# SX1262_e428v03a.net
KiCad netlist of a schematic drawn in Altium Designer
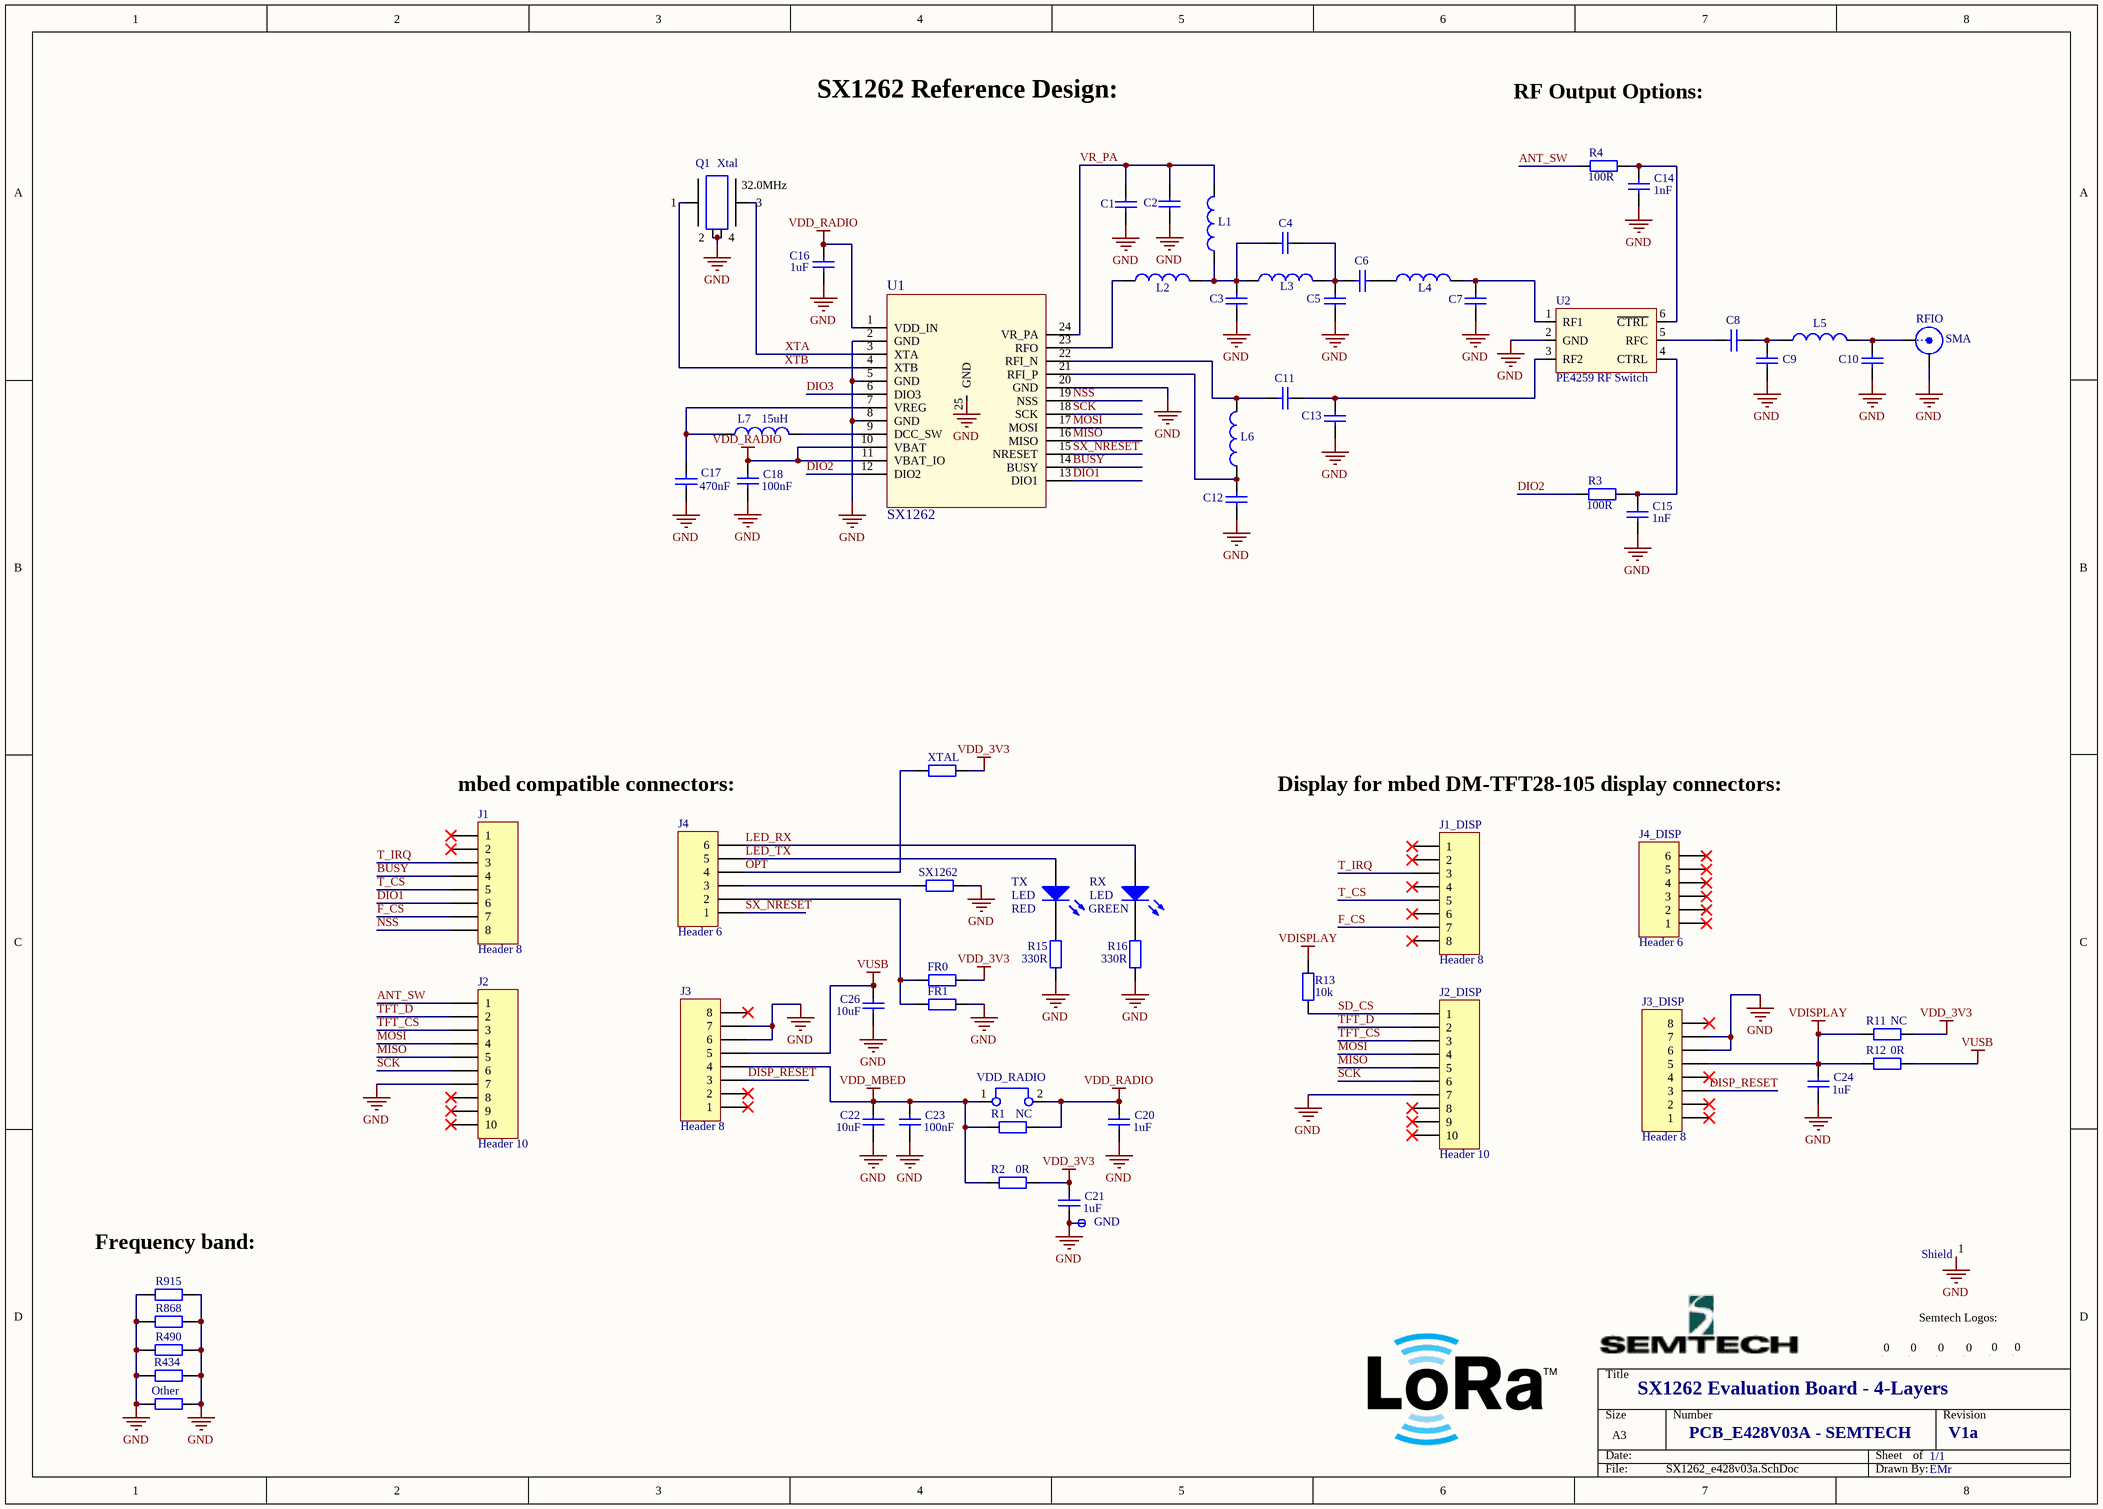
[diagram p0: SX1262_e428v03a.SchDoc]

(export (version "E")
  (design (tool "Eeschema 10.0.6"))
  (components
    (comp (ref "C1")
      (value "Cap")
      (footprint "rlc_402_smd")
      (description "Capacitor SMD")
      (fields (field (name "PUBLISHER") "Altium Limited"))
      (libsource (lib "SX1262_e428v03a") (part "Cap"))
    )
    (comp (ref "C2")
      (value "Cap")
      (footprint "rlc_402_smd")
      (description "Capacitor SMD")
      (fields (field (name "PUBLISHER") "Altium Limited"))
      (libsource (lib "SX1262_e428v03a") (part "Cap"))
    )
    (comp (ref "C3")
      (value "Cap")
      (footprint "rlc_402_smd")
      (description "Capacitor SMD")
      (fields (field (name "PUBLISHER") "Altium Limited"))
      (libsource (lib "SX1262_e428v03a") (part "Cap"))
    )
    (comp (ref "C4")
      (value "Cap")
      (footprint "rlc_402_smd")
      (description "Capacitor SMD")
      (fields (field (name "PUBLISHER") "Altium Limited"))
      (libsource (lib "SX1262_e428v03a") (part "Cap"))
    )
    (comp (ref "C5")
      (value "Cap")
      (footprint "rlc_402_smd")
      (description "Capacitor SMD")
      (fields (field (name "PUBLISHER") "Altium Limited"))
      (libsource (lib "SX1262_e428v03a") (part "Cap"))
    )
    (comp (ref "C6")
      (value "Cap")
      (footprint "rlc_402_smd")
      (description "Capacitor SMD")
      (fields (field (name "PUBLISHER") "Altium Limited"))
      (libsource (lib "SX1262_e428v03a") (part "Cap"))
    )
    (comp (ref "C7")
      (value "Cap")
      (footprint "rlc_402_smd")
      (description "Capacitor SMD")
      (fields (field (name "PUBLISHER") "Altium Limited"))
      (libsource (lib "SX1262_e428v03a") (part "Cap"))
    )
    (comp (ref "C8")
      (value "Cap")
      (footprint "rlc_402_smd")
      (description "Capacitor SMD")
      (fields (field (name "PUBLISHER") "Altium Limited"))
      (libsource (lib "SX1262_e428v03a") (part "Cap"))
    )
    (comp (ref "C9")
      (value "Cap")
      (footprint "rlc_402_smd")
      (description "Capacitor SMD")
      (fields (field (name "PUBLISHER") "Altium Limited"))
      (libsource (lib "SX1262_e428v03a") (part "Cap"))
    )
    (comp (ref "C10")
      (value "Cap")
      (footprint "rlc_402_smd")
      (description "Capacitor SMD")
      (fields (field (name "PUBLISHER") "Altium Limited"))
      (libsource (lib "SX1262_e428v03a") (part "Cap"))
    )
    (comp (ref "C11")
      (value "Cap")
      (footprint "rlc_402_smd")
      (description "Capacitor SMD")
      (fields (field (name "PUBLISHER") "Altium Limited"))
      (libsource (lib "SX1262_e428v03a") (part "Cap"))
    )
    (comp (ref "C12")
      (value "Cap")
      (footprint "rlc_402_smd")
      (description "Capacitor SMD")
      (fields (field (name "PUBLISHER") "Altium Limited"))
      (libsource (lib "SX1262_e428v03a") (part "Cap"))
    )
    (comp (ref "C13")
      (value "Cap")
      (footprint "rlc_402_smd")
      (description "Capacitor SMD")
      (fields (field (name "PUBLISHER") "Altium Limited"))
      (libsource (lib "SX1262_e428v03a") (part "Cap"))
    )
    (comp (ref "C14")
      (value "1nF")
      (footprint "rlc_402_smd")
      (description "Capacitor SMD")
      (fields (field (name "Comment") "Cap") (field (name "PUBLISHER") "Altium Limited"))
      (libsource (lib "SX1262_e428v03a") (part "Cap"))
    )
    (comp (ref "C15")
      (value "1nF")
      (footprint "rlc_402_smd")
      (description "Capacitor SMD")
      (fields (field (name "Comment") "Cap") (field (name "PUBLISHER") "Altium Limited"))
      (libsource (lib "SX1262_e428v03a") (part "Cap"))
    )
    (comp (ref "C16")
      (value "1uF")
      (footprint "rlc_402_smd")
      (description "Capacitor SMD")
      (fields (field (name "Comment") "Cap") (field (name "PUBLISHER") "Altium Limited"))
      (libsource (lib "SX1262_e428v03a") (part "Cap"))
    )
    (comp (ref "C17")
      (value "470nF")
      (footprint "rlc_402_smd")
      (description "Capacitor SMD")
      (fields (field (name "Comment") "Cap") (field (name "PUBLISHER") "Altium Limited"))
      (libsource (lib "SX1262_e428v03a") (part "Cap"))
    )
    (comp (ref "C18")
      (value "100nF")
      (footprint "rlc_402_smd")
      (description "Capacitor SMD")
      (fields (field (name "Comment") "Cap") (field (name "PUBLISHER") "Altium Limited"))
      (libsource (lib "SX1262_e428v03a") (part "Cap"))
    )
    (comp (ref "C20")
      (value "1uF")
      (footprint "rlc_603_smd")
      (description "Capacitor SMD")
      (fields (field (name "Comment") "Cap") (field (name "PUBLISHER") "Altium Limited"))
      (libsource (lib "SX1262_e428v03a") (part "Cap"))
    )
    (comp (ref "C21")
      (value "1uF")
      (footprint "rlc_603_smd")
      (description "Capacitor SMD")
      (fields (field (name "Comment") "Cap") (field (name "PUBLISHER") "Altium Limited"))
      (libsource (lib "SX1262_e428v03a") (part "Cap"))
    )
    (comp (ref "C22")
      (value "10uF")
      (footprint "rlc_805_smd")
      (description "Capacitor SMD")
      (fields (field (name "Comment") "Cap") (field (name "PUBLISHER") "Altium Limited"))
      (libsource (lib "SX1262_e428v03a") (part "Cap"))
    )
    (comp (ref "C23")
      (value "100nF")
      (footprint "rlc_402_smd")
      (description "Capacitor SMD")
      (fields (field (name "Comment") "Cap") (field (name "PUBLISHER") "Altium Limited"))
      (libsource (lib "SX1262_e428v03a") (part "Cap"))
    )
    (comp (ref "C24")
      (value "1uF")
      (footprint "rlc_402_smd")
      (description "Capacitor SMD")
      (fields (field (name "Comment") "Cap") (field (name "PUBLISHER") "Altium Limited"))
      (libsource (lib "SX1262_e428v03a") (part "Cap"))
    )
    (comp (ref "C26")
      (value "10uF")
      (footprint "rlc_805_smd")
      (description "Capacitor SMD")
      (fields (field (name "Comment") "Cap") (field (name "PUBLISHER") "Altium Limited"))
      (libsource (lib "SX1262_e428v03a") (part "Cap"))
    )
    (comp (ref "FR0")
      (value "Resistor")
      (footprint "rlc_402_smd")
      (description "Resistor SMD - IEC symbol version")
      (libsource (lib "SX1262_e428v03a") (part "Resistor"))
    )
    (comp (ref "FR1")
      (value "Resistor")
      (footprint "rlc_402_smd")
      (description "Resistor SMD - IEC symbol version")
      (libsource (lib "SX1262_e428v03a") (part "Resistor"))
    )
    (comp (ref "GND")
      (value "Test Pin")
      (footprint "pin_0.9mm")
      (libsource (lib "SX1262_e428v03a") (part "test_pin"))
    )
    (comp (ref "J1")
      (value "Header 8")
      (footprint "HDR1X8")
      (description "Header, 8-Pin")
      (fields (field (name "PUBLISHER") "Altium Limited"))
      (libsource (lib "SX1262_e428v03a") (part "Header 8"))
    )
    (comp (ref "J1_DISP")
      (value "Header 8")
      (footprint "HDR1X8")
      (description "Header, 8-Pin")
      (fields (field (name "PUBLISHER") "Altium Limited"))
      (libsource (lib "SX1262_e428v03a") (part "Header 8"))
    )
    (comp (ref "J2")
      (value "Header 10")
      (footprint "HDR1X10")
      (description "Header, 10-Pin")
      (fields (field (name "PUBLISHER") "Altium Limited"))
      (libsource (lib "SX1262_e428v03a") (part "Header 10"))
    )
    (comp (ref "J2_DISP")
      (value "Header 10")
      (footprint "HDR1X10")
      (description "Header, 10-Pin")
      (fields (field (name "PUBLISHER") "Altium Limited"))
      (libsource (lib "SX1262_e428v03a") (part "Header 10"))
    )
    (comp (ref "J3")
      (value "Header 8")
      (footprint "HDR1X8")
      (description "Header, 8-Pin")
      (fields (field (name "PUBLISHER") "Altium Limited"))
      (libsource (lib "") (part "Header 8_1"))
    )
    (comp (ref "J3_DISP")
      (value "Header 8")
      (footprint "HDR1X8")
      (description "Header, 8-Pin")
      (fields (field (name "PUBLISHER") "Altium Limited"))
      (libsource (lib "") (part "Header 8_1"))
    )
    (comp (ref "J4")
      (value "Header 6")
      (footprint "HDR1X6")
      (description "Header, 6-Pin")
      (fields (field (name "PUBLISHER") "Altium Limited"))
      (libsource (lib "SX1262_e428v03a") (part "Header 6"))
    )
    (comp (ref "J4_DISP")
      (value "Header 6")
      (footprint "HDR1X6")
      (description "Header, 6-Pin")
      (fields (field (name "PUBLISHER") "Altium Limited"))
      (libsource (lib "SX1262_e428v03a") (part "Header 6"))
    )
    (comp (ref "L1")
      (value "Inductor")
      (footprint "rlc_402_smd")
      (description "Inductor SMD")
      (fields (field (name "PUBLISHER") "Altium Limited"))
      (libsource (lib "SX1262_e428v03a") (part "Inductor"))
    )
    (comp (ref "L2")
      (value "Inductor")
      (footprint "rlc_402_smd")
      (description "Inductor SMD")
      (fields (field (name "PUBLISHER") "Altium Limited"))
      (libsource (lib "SX1262_e428v03a") (part "Inductor"))
    )
    (comp (ref "L3")
      (value "Inductor")
      (footprint "rlc_402_smd")
      (description "Inductor SMD")
      (fields (field (name "PUBLISHER") "Altium Limited"))
      (libsource (lib "SX1262_e428v03a") (part "Inductor"))
    )
    (comp (ref "L4")
      (value "Inductor")
      (footprint "rlc_402_smd")
      (description "Inductor SMD")
      (fields (field (name "PUBLISHER") "Altium Limited"))
      (libsource (lib "SX1262_e428v03a") (part "Inductor"))
    )
    (comp (ref "L5")
      (value "Inductor")
      (footprint "rlc_402_smd")
      (description "Inductor SMD")
      (fields (field (name "PUBLISHER") "Altium Limited"))
      (libsource (lib "SX1262_e428v03a") (part "Inductor"))
    )
    (comp (ref "L6")
      (value "Inductor")
      (footprint "rlc_402_smd")
      (description "Inductor SMD")
      (fields (field (name "PUBLISHER") "Altium Limited"))
      (libsource (lib "SX1262_e428v03a") (part "Inductor"))
    )
    (comp (ref "L7")
      (value "15uH")
      (footprint "rlc_805_smd enlarged")
      (description "Inductor SMD")
      (fields (field (name "Comment") "Inductor") (field (name "PUBLISHER") "Altium Limited"))
      (libsource (lib "SX1262_e428v03a") (part "Inductor"))
    )
    (comp (ref "Logo Bot")
      (value "Logo symbol")
      (footprint "logo_semtech_horiz_size4")
      (description "Schematic symbol for Logo")
      (libsource (lib "SX1262_e428v03a") (part "Logo"))
    )
    (comp (ref "Logo ESD")
      (value "Logo symbol")
      (footprint "Logo ESD")
      (description "Schematic symbol for Logo")
      (libsource (lib "SX1262_e428v03a") (part "Logo"))
    )
    (comp (ref "Logo Recycling1")
      (value "Logo symbol")
      (footprint "Logo Recycling1")
      (description "Schematic symbol for Logo")
      (libsource (lib "SX1262_e428v03a") (part "Logo"))
    )
    (comp (ref "Logo Semtech S")
      (value "Logo symbol")
      (footprint "logo_semtech_horiz_size3")
      (description "Schematic symbol for Logo")
      (libsource (lib "SX1262_e428v03a") (part "Logo"))
    )
    (comp (ref "Logo_LoRA1")
      (value "Logo symbol")
      (footprint "Logo LoRa Size4")
      (description "Schematic symbol for Logo")
      (libsource (lib "SX1262_e428v03a") (part "Logo"))
    )
    (comp (ref "Logo_LoRA2")
      (value "Logo symbol")
      (footprint "Logo LoRa Size3")
      (description "Schematic symbol for Logo")
      (libsource (lib "SX1262_e428v03a") (part "Logo"))
    )
    (comp (ref "Other")
      (value "Resistor")
      (footprint "rlc_402_smd")
      (description "Resistor SMD - IEC symbol version")
      (libsource (lib "") (part "Resistor_1"))
    )
    (comp (ref "Q1")
      (value "Xtal")
      (footprint "nd2016da")
      (description "Crystal with GND pins")
      (fields (field (name "ALTIUM_VALUE") "32.0MHz"))
      (libsource (lib "SX1262_e428v03a") (part "Xtal GND"))
    )
    (comp (ref "R1")
      (value "NC")
      (footprint "rlc_603_smd")
      (description "Resistor SMD - IEC symbol version")
      (fields (field (name "Comment") "Resistor"))
      (libsource (lib "") (part "Resistor_1"))
    )
    (comp (ref "R2")
      (value "0R")
      (footprint "rlc_603_smd")
      (description "Resistor SMD - IEC symbol version")
      (fields (field (name "Comment") "Resistor"))
      (libsource (lib "") (part "Resistor_1"))
    )
    (comp (ref "R3")
      (value "100R")
      (footprint "rlc_402_smd")
      (description "Resistor SMD - IEC symbol version")
      (fields (field (name "Comment") "Resistor"))
      (libsource (lib "") (part "Resistor_1"))
    )
    (comp (ref "R4")
      (value "100R")
      (footprint "rlc_402_smd")
      (description "Resistor SMD - IEC symbol version")
      (fields (field (name "Comment") "Resistor"))
      (libsource (lib "") (part "Resistor_1"))
    )
    (comp (ref "R11")
      (value "NC")
      (footprint "rlc_402_smd")
      (description "Resistor SMD - IEC symbol version")
      (fields (field (name "Comment") "Resistor"))
      (libsource (lib "") (part "Resistor_1"))
    )
    (comp (ref "R12")
      (value "0R")
      (footprint "rlc_402_smd")
      (description "Resistor SMD - IEC symbol version")
      (fields (field (name "Comment") "Resistor"))
      (libsource (lib "") (part "Resistor_1"))
    )
    (comp (ref "R13")
      (value "10k")
      (footprint "rlc_402_smd")
      (description "Resistor SMD - IEC symbol version")
      (fields (field (name "Comment") "Resistor"))
      (libsource (lib "") (part "Resistor_1"))
    )
    (comp (ref "R15")
      (value "330R")
      (footprint "rlc_402_smd")
      (description "Resistor SMD - IEC symbol version")
      (fields (field (name "Comment") "Resistor"))
      (libsource (lib "") (part "Resistor_2"))
    )
    (comp (ref "R16")
      (value "330R")
      (footprint "rlc_402_smd")
      (description "Resistor SMD - IEC symbol version")
      (fields (field (name "Comment") "Resistor"))
      (libsource (lib "") (part "Resistor_2"))
    )
    (comp (ref "R434")
      (value "Resistor")
      (footprint "rlc_402_smd")
      (description "Resistor SMD - IEC symbol version")
      (libsource (lib "") (part "Resistor_1"))
    )
    (comp (ref "R490")
      (value "Resistor")
      (footprint "rlc_402_smd")
      (description "Resistor SMD - IEC symbol version")
      (libsource (lib "") (part "Resistor_1"))
    )
    (comp (ref "R868")
      (value "Resistor")
      (footprint "rlc_402_smd")
      (description "Resistor SMD - IEC symbol version")
      (libsource (lib "") (part "Resistor_1"))
    )
    (comp (ref "R915")
      (value "Resistor")
      (footprint "rlc_402_smd")
      (description "Resistor SMD - IEC symbol version")
      (libsource (lib "") (part "Resistor_1"))
    )
    (comp (ref "RFIO")
      (value "SMA")
      (footprint "SMA_end_launch_1.0mm_9.52mm")
      (description "SMA Straight Connector")
      (fields (field (name "PUBLISHER") "Altium Limited"))
      (libsource (lib "SX1262_e428v03a") (part "SMA"))
    )
    (comp (ref "RX")
      (value "LED")
      (footprint "LGM676 LED")
      (fields (field (name "ALTIUM_VALUE") "GREEN"))
      (libsource (lib "SX1262_e428v03a") (part "LED"))
    )
    (comp (ref "Shield")
      (value "Logo symbol")
      (footprint "BMIS-209-F - Shield - Solder_Mask")
      (description "Shield - EMI Gasket - Standard Surface Mount Shields")
      (libsource (lib "SX1262_e428v03a") (part "Shield"))
    )
    (comp (ref "SX1262")
      (value "Resistor")
      (footprint "rlc_402_smd")
      (description "Resistor SMD - IEC symbol version")
      (libsource (lib "SX1262_e428v03a") (part "Resistor"))
    )
    (comp (ref "TX")
      (value "LED")
      (footprint "LGM676 LED")
      (fields (field (name "ALTIUM_VALUE") "RED"))
      (libsource (lib "SX1262_e428v03a") (part "LED"))
    )
    (comp (ref "U1")
      (value "SX1262")
      (footprint "vqfn24_4x4mm")
      (description "SX1262- Ultra low power RF transceiver")
      (libsource (lib "SX1262_e428v03a") (part "SX126x"))
    )
    (comp (ref "U2")
      (value "PE4259 RF Switch")
      (footprint "SC70-6")
      (description "PE4259 Peregrine RF Switch")
      (libsource (lib "SX1262_e428v03a") (part "PE4259 RF Switch"))
    )
    (comp (ref "VDD_RADIO")
      (value "Jumper")
      (footprint "bridge_254mm")
      (description "Jumper Wire")
      (libsource (lib "SX1262_e428v03a") (part "Jumper"))
    )
    (comp (ref "XTAL")
      (value "Resistor")
      (footprint "rlc_402_smd")
      (description "Resistor SMD - IEC symbol version")
      (libsource (lib "SX1262_e428v03a") (part "Resistor"))
    )
  )
  (nets
    (net (code "1") (name "/ANT_SW") (class "Default")
      (node (ref "J2") (pin "1") (pinfunction "1_1") (pintype "passive"))
      (node (ref "R4") (pin "2") (pinfunction "2_2") (pintype "passive"))
    )
    (net (code "2") (name "/BUSY") (class "Default")
      (node (ref "J1") (pin "4") (pinfunction "4_4") (pintype "passive"))
      (node (ref "U1") (pin "14") (pinfunction "BUSY_14") (pintype "passive"))
    )
    (net (code "3") (name "/DIO1") (class "Default")
      (node (ref "J1") (pin "6") (pinfunction "6_6") (pintype "passive"))
      (node (ref "U1") (pin "13") (pinfunction "DIO1_13") (pintype "passive"))
    )
    (net (code "4") (name "/DIO2") (class "Default")
      (node (ref "R3") (pin "2") (pinfunction "2_2") (pintype "passive"))
      (node (ref "U1") (pin "12") (pinfunction "DIO2_12") (pintype "passive"))
    )
    (net (code "5") (name "/DIO3") (class "Default")
      (node (ref "U1") (pin "6") (pinfunction "DIO3_6") (pintype "passive"))
    )
    (net (code "6") (name "/DISP_RESET") (class "Default")
      (node (ref "J3") (pin "3") (pinfunction "3_3") (pintype "passive"))
      (node (ref "J3_DISP") (pin "3") (pinfunction "3_3") (pintype "passive"))
    )
    (net (code "7") (name "/F_CS") (class "Default")
      (node (ref "J1") (pin "7") (pinfunction "7_7") (pintype "passive"))
      (node (ref "J1_DISP") (pin "7") (pinfunction "7_7") (pintype "passive"))
    )
    (net (code "8") (name "/LED_RX") (class "Default")
      (node (ref "J4") (pin "6") (pinfunction "6_6") (pintype "passive"))
      (node (ref "RX") (pin "1") (pinfunction "A_1") (pintype "passive"))
    )
    (net (code "9") (name "/LED_TX") (class "Default")
      (node (ref "J4") (pin "5") (pinfunction "5_5") (pintype "passive"))
      (node (ref "TX") (pin "1") (pinfunction "A_1") (pintype "passive"))
    )
    (net (code "10") (name "/MISO") (class "Default")
      (node (ref "J2") (pin "5") (pinfunction "5_5") (pintype "passive"))
      (node (ref "J2_DISP") (pin "5") (pinfunction "5_5") (pintype "passive"))
      (node (ref "U1") (pin "16") (pinfunction "MISO_16") (pintype "passive"))
    )
    (net (code "11") (name "/MOSI") (class "Default")
      (node (ref "J2") (pin "4") (pinfunction "4_4") (pintype "passive"))
      (node (ref "J2_DISP") (pin "4") (pinfunction "4_4") (pintype "passive"))
      (node (ref "U1") (pin "17") (pinfunction "MOSI_17") (pintype "passive"))
    )
    (net (code "12") (name "/NSS") (class "Default")
      (node (ref "J1") (pin "8") (pinfunction "8_8") (pintype "passive"))
      (node (ref "U1") (pin "19") (pinfunction "NSS_19") (pintype "passive"))
    )
    (net (code "13") (name "/OPT") (class "Default")
      (node (ref "J4") (pin "4") (pinfunction "4_4") (pintype "passive"))
      (node (ref "XTAL") (pin "2") (pinfunction "2_2") (pintype "passive"))
    )
    (net (code "14") (name "/SCK") (class "Default")
      (node (ref "J2") (pin "6") (pinfunction "6_6") (pintype "passive"))
      (node (ref "J2_DISP") (pin "6") (pinfunction "6_6") (pintype "passive"))
      (node (ref "U1") (pin "18") (pinfunction "SCK_18") (pintype "passive"))
    )
    (net (code "15") (name "/SD_CS") (class "Default")
      (node (ref "J2_DISP") (pin "1") (pinfunction "1_1") (pintype "passive"))
      (node (ref "R13") (pin "2") (pinfunction "2_2") (pintype "passive"))
    )
    (net (code "16") (name "/SX_NRESET") (class "Default")
      (node (ref "J4") (pin "1") (pinfunction "1_1") (pintype "passive"))
      (node (ref "U1") (pin "15") (pinfunction "NRESET_15") (pintype "passive"))
    )
    (net (code "17") (name "/TFT_CS") (class "Default")
      (node (ref "J2") (pin "3") (pinfunction "3_3") (pintype "passive"))
      (node (ref "J2_DISP") (pin "3") (pinfunction "3_3") (pintype "passive"))
    )
    (net (code "18") (name "/TFT_D") (class "Default")
      (node (ref "J2") (pin "2") (pinfunction "2_2") (pintype "passive"))
      (node (ref "J2_DISP") (pin "2") (pinfunction "2_2") (pintype "passive"))
    )
    (net (code "19") (name "/T_CS") (class "Default")
      (node (ref "J1") (pin "5") (pinfunction "5_5") (pintype "passive"))
      (node (ref "J1_DISP") (pin "5") (pinfunction "5_5") (pintype "passive"))
    )
    (net (code "20") (name "/T_IRQ") (class "Default")
      (node (ref "J1") (pin "3") (pinfunction "3_3") (pintype "passive"))
      (node (ref "J1_DISP") (pin "3") (pinfunction "3_3") (pintype "passive"))
    )
    (net (code "21") (name "/VR_PA") (class "Default")
      (node (ref "C1") (pin "2") (pinfunction "2_2") (pintype "passive"))
      (node (ref "C2") (pin "2") (pinfunction "2_2") (pintype "passive"))
      (node (ref "L1") (pin "2") (pinfunction "2_2") (pintype "passive"))
      (node (ref "U1") (pin "24") (pinfunction "VR_PA_24") (pintype "power_in"))
    )
    (net (code "22") (name "/XTA") (class "Default")
      (node (ref "Q1") (pin "3") (pinfunction "3_3") (pintype "passive"))
      (node (ref "U1") (pin "3") (pinfunction "XTA_3") (pintype "passive"))
    )
    (net (code "24") (name "/XTB") (class "Default")
      (node (ref "Q1") (pin "1") (pinfunction "1_1") (pintype "passive"))
      (node (ref "U1") (pin "4") (pinfunction "XTB_4") (pintype "passive"))
    )
    (net (code "25") (name "GND") (class "Default")
      (node (ref "C1") (pin "1") (pinfunction "1_1") (pintype "passive"))
      (node (ref "C10") (pin "1") (pinfunction "1_1") (pintype "passive"))
      (node (ref "C12") (pin "1") (pinfunction "1_1") (pintype "passive"))
      (node (ref "C13") (pin "1") (pinfunction "1_1") (pintype "passive"))
      (node (ref "C14") (pin "2") (pinfunction "2_2") (pintype "passive"))
      (node (ref "C15") (pin "2") (pinfunction "2_2") (pintype "passive"))
      (node (ref "C16") (pin "1") (pinfunction "1_1") (pintype "passive"))
      (node (ref "C17") (pin "1") (pinfunction "1_1") (pintype "passive"))
      (node (ref "C18") (pin "1") (pinfunction "1_1") (pintype "passive"))
      (node (ref "C2") (pin "1") (pinfunction "1_1") (pintype "passive"))
      (node (ref "C20") (pin "1") (pinfunction "1_1") (pintype "passive"))
      (node (ref "C21") (pin "1") (pinfunction "1_1") (pintype "passive"))
      (node (ref "C22") (pin "1") (pinfunction "1_1") (pintype "passive"))
      (node (ref "C23") (pin "1") (pinfunction "1_1") (pintype "passive"))
      (node (ref "C24") (pin "1") (pinfunction "1_1") (pintype "passive"))
      (node (ref "C26") (pin "1") (pinfunction "1_1") (pintype "passive"))
      (node (ref "C3") (pin "1") (pinfunction "1_1") (pintype "passive"))
      (node (ref "C5") (pin "1") (pinfunction "1_1") (pintype "passive"))
      (node (ref "C7") (pin "1") (pinfunction "1_1") (pintype "passive"))
      (node (ref "C9") (pin "1") (pinfunction "1_1") (pintype "passive"))
      (node (ref "FR1") (pin "1") (pinfunction "1_1") (pintype "passive"))
      (node (ref "GND") (pin "1") (pinfunction "pin_1") (pintype "passive"))
      (node (ref "J2") (pin "7") (pinfunction "7_7") (pintype "passive"))
      (node (ref "J2_DISP") (pin "7") (pinfunction "7_7") (pintype "passive"))
      (node (ref "J3") (pin "6") (pinfunction "6_6") (pintype "passive"))
      (node (ref "J3") (pin "7") (pinfunction "7_7") (pintype "passive"))
      (node (ref "J3_DISP") (pin "6") (pinfunction "6_6") (pintype "passive"))
      (node (ref "J3_DISP") (pin "7") (pinfunction "7_7") (pintype "passive"))
      (node (ref "Other") (pin "1") (pinfunction "1_1") (pintype "passive"))
      (node (ref "Other") (pin "2") (pinfunction "2_2") (pintype "passive"))
      (node (ref "Q1") (pin "2") (pinfunction "2_2") (pintype "passive"))
      (node (ref "Q1") (pin "4") (pinfunction "4_4") (pintype "passive"))
      (node (ref "R15") (pin "1") (pinfunction "1_1") (pintype "passive"))
      (node (ref "R16") (pin "1") (pinfunction "1_1") (pintype "passive"))
      (node (ref "R434") (pin "1") (pinfunction "1_1") (pintype "passive"))
      (node (ref "R434") (pin "2") (pinfunction "2_2") (pintype "passive"))
      (node (ref "R490") (pin "1") (pinfunction "1_1") (pintype "passive"))
      (node (ref "R490") (pin "2") (pinfunction "2_2") (pintype "passive"))
      (node (ref "R868") (pin "1") (pinfunction "1_1") (pintype "passive"))
      (node (ref "R868") (pin "2") (pinfunction "2_2") (pintype "passive"))
      (node (ref "R915") (pin "1") (pinfunction "1_1") (pintype "passive"))
      (node (ref "R915") (pin "2") (pinfunction "2_2") (pintype "passive"))
      (node (ref "RFIO") (pin "2") (pinfunction "GND_2") (pintype "passive"))
      (node (ref "SX1262") (pin "1") (pinfunction "1_1") (pintype "passive"))
      (node (ref "Shield") (pin "1") (pinfunction "1_1") (pintype "passive"))
      (node (ref "U1") (pin "2") (pinfunction "GND_2") (pintype "passive"))
      (node (ref "U1") (pin "20") (pinfunction "GND_20") (pintype "passive"))
      (node (ref "U1") (pin "25") (pinfunction "GND_25") (pintype "passive"))
      (node (ref "U1") (pin "5") (pinfunction "GND_5") (pintype "passive"))
      (node (ref "U1") (pin "8") (pinfunction "GND_8") (pintype "passive"))
      (node (ref "U2") (pin "2") (pinfunction "GND_2") (pintype "passive"))
    )
    (net (code "26") (name "Net-(C3-Pad2)") (class "Default")
      (node (ref "C3") (pin "2") (pinfunction "2_2") (pintype "passive"))
      (node (ref "C4") (pin "2") (pinfunction "2_2") (pintype "passive"))
      (node (ref "L1") (pin "1") (pinfunction "1_1") (pintype "passive"))
      (node (ref "L2") (pin "2") (pinfunction "2_2") (pintype "passive"))
      (node (ref "L3") (pin "1") (pinfunction "1_1") (pintype "passive"))
    )
    (net (code "27") (name "Net-(C4-Pad1)") (class "Default")
      (node (ref "C4") (pin "1") (pinfunction "1_1") (pintype "passive"))
      (node (ref "C5") (pin "2") (pinfunction "2_2") (pintype "passive"))
      (node (ref "C6") (pin "2") (pinfunction "2_2") (pintype "passive"))
      (node (ref "L3") (pin "2") (pinfunction "2_2") (pintype "passive"))
    )
    (net (code "28") (name "Net-(C6-Pad1)") (class "Default")
      (node (ref "C6") (pin "1") (pinfunction "1_1") (pintype "passive"))
      (node (ref "L4") (pin "1") (pinfunction "1_1") (pintype "passive"))
    )
    (net (code "29") (name "Net-(C8-Pad1)") (class "Default")
      (node (ref "C8") (pin "1") (pinfunction "1_1") (pintype "passive"))
      (node (ref "C9") (pin "2") (pinfunction "2_2") (pintype "passive"))
      (node (ref "L5") (pin "1") (pinfunction "1_1") (pintype "passive"))
    )
    (net (code "30") (name "Net-(FR0-Pad2)") (class "Default")
      (node (ref "FR0") (pin "2") (pinfunction "2_2") (pintype "passive"))
      (node (ref "FR1") (pin "2") (pinfunction "2_2") (pintype "passive"))
      (node (ref "J4") (pin "2") (pinfunction "2_2") (pintype "passive"))
    )
    (net (code "31") (name "Net-(J4-Pad3)") (class "Default")
      (node (ref "J4") (pin "3") (pinfunction "3_3") (pintype "passive"))
      (node (ref "SX1262") (pin "2") (pinfunction "2_2") (pintype "passive"))
    )
    (net (code "32") (name "Net-(RFIO-Signal)") (class "Default")
      (node (ref "C10") (pin "2") (pinfunction "2_2") (pintype "passive"))
      (node (ref "L5") (pin "2") (pinfunction "2_2") (pintype "passive"))
      (node (ref "RFIO") (pin "1") (pinfunction "Signal_1") (pintype "passive"))
    )
    (net (code "33") (name "Net-(RX-K)") (class "Default")
      (node (ref "R16") (pin "2") (pinfunction "2_2") (pintype "passive"))
      (node (ref "RX") (pin "2") (pinfunction "K_2") (pintype "passive"))
    )
    (net (code "34") (name "Net-(TX-K)") (class "Default")
      (node (ref "R15") (pin "2") (pinfunction "2_2") (pintype "passive"))
      (node (ref "TX") (pin "2") (pinfunction "K_2") (pintype "passive"))
    )
    (net (code "35") (name "Net-(U1-DCC_SW)") (class "Default")
      (node (ref "L7") (pin "2") (pinfunction "2_2") (pintype "passive"))
      (node (ref "U1") (pin "9") (pinfunction "DCC_SW_9") (pintype "power_in"))
    )
    (net (code "36") (name "Net-(U1-RFI_N)") (class "Default")
      (node (ref "C11") (pin "2") (pinfunction "2_2") (pintype "passive"))
      (node (ref "L6") (pin "2") (pinfunction "2_2") (pintype "passive"))
      (node (ref "U1") (pin "22") (pinfunction "RFI_N_22") (pintype "passive"))
    )
    (net (code "37") (name "Net-(U1-RFI_P)") (class "Default")
      (node (ref "C12") (pin "2") (pinfunction "2_2") (pintype "passive"))
      (node (ref "L6") (pin "1") (pinfunction "1_1") (pintype "passive"))
      (node (ref "U1") (pin "21") (pinfunction "RFI_P_21") (pintype "passive"))
    )
    (net (code "38") (name "Net-(U1-RFO)") (class "Default")
      (node (ref "L2") (pin "1") (pinfunction "1_1") (pintype "passive"))
      (node (ref "U1") (pin "23") (pinfunction "RFO_23") (pintype "passive"))
    )
    (net (code "39") (name "Net-(U1-VREG)") (class "Default")
      (node (ref "C17") (pin "2") (pinfunction "2_2") (pintype "passive"))
      (node (ref "L7") (pin "1") (pinfunction "1_1") (pintype "passive"))
      (node (ref "U1") (pin "7") (pinfunction "VREG_7") (pintype "power_in"))
    )
    (net (code "40") (name "Net-(U2-CTRL)") (class "Default")
      (node (ref "C15") (pin "1") (pinfunction "1_1") (pintype "passive"))
      (node (ref "R3") (pin "1") (pinfunction "1_1") (pintype "passive"))
      (node (ref "U2") (pin "4") (pinfunction "CTRL_4") (pintype "passive"))
    )
    (net (code "41") (name "Net-(U2-RF1)") (class "Default")
      (node (ref "C7") (pin "2") (pinfunction "2_2") (pintype "passive"))
      (node (ref "L4") (pin "2") (pinfunction "2_2") (pintype "passive"))
      (node (ref "U2") (pin "1") (pinfunction "RF1_1") (pintype "passive"))
    )
    (net (code "42") (name "Net-(U2-RF2)") (class "Default")
      (node (ref "C11") (pin "1") (pinfunction "1_1") (pintype "passive"))
      (node (ref "C13") (pin "2") (pinfunction "2_2") (pintype "passive"))
      (node (ref "U2") (pin "3") (pinfunction "RF2_3") (pintype "passive"))
    )
    (net (code "43") (name "Net-(U2-RFC)") (class "Default")
      (node (ref "C8") (pin "2") (pinfunction "2_2") (pintype "passive"))
      (node (ref "U2") (pin "5") (pinfunction "RFC_5") (pintype "passive"))
    )
    (net (code "44") (name "Net-(U2-~{CTRL})") (class "Default")
      (node (ref "C14") (pin "1") (pinfunction "1_1") (pintype "passive"))
      (node (ref "R4") (pin "1") (pinfunction "1_1") (pintype "passive"))
      (node (ref "U2") (pin "6") (pinfunction "~{CTRL}_6") (pintype "passive"))
    )
    (net (code "45") (name "VDD_3V3") (class "Default")
      (node (ref "C21") (pin "2") (pinfunction "2_2") (pintype "passive"))
      (node (ref "FR0") (pin "1") (pinfunction "1_1") (pintype "passive"))
      (node (ref "R11") (pin "1") (pinfunction "1_1") (pintype "passive"))
      (node (ref "R2") (pin "1") (pinfunction "1_1") (pintype "passive"))
      (node (ref "XTAL") (pin "1") (pinfunction "1_1") (pintype "passive"))
    )
    (net (code "46") (name "VDD_MBED") (class "Default")
      (node (ref "C22") (pin "2") (pinfunction "2_2") (pintype "passive"))
      (node (ref "C23") (pin "2") (pinfunction "2_2") (pintype "passive"))
      (node (ref "J3") (pin "4") (pinfunction "4_4") (pintype "passive"))
      (node (ref "R1") (pin "2") (pinfunction "2_2") (pintype "passive"))
      (node (ref "R2") (pin "2") (pinfunction "2_2") (pintype "passive"))
      (node (ref "VDD_RADIO") (pin "1") (pinfunction "1_1") (pintype "passive"))
    )
    (net (code "47") (name "VDD_RADIO") (class "Default")
      (node (ref "C16") (pin "2") (pinfunction "2_2") (pintype "passive"))
      (node (ref "C18") (pin "2") (pinfunction "2_2") (pintype "passive"))
      (node (ref "C20") (pin "2") (pinfunction "2_2") (pintype "passive"))
      (node (ref "R1") (pin "1") (pinfunction "1_1") (pintype "passive"))
      (node (ref "U1") (pin "1") (pinfunction "VDD_IN_1") (pintype "power_in"))
      (node (ref "U1") (pin "10") (pinfunction "VBAT_10") (pintype "power_in"))
      (node (ref "U1") (pin "11") (pinfunction "VBAT_IO_11") (pintype "power_in"))
      (node (ref "VDD_RADIO") (pin "2") (pinfunction "2_2") (pintype "passive"))
    )
    (net (code "48") (name "VDISPLAY") (class "Default")
      (node (ref "C24") (pin "2") (pinfunction "2_2") (pintype "passive"))
      (node (ref "J3_DISP") (pin "5") (pinfunction "5_5") (pintype "passive"))
      (node (ref "R11") (pin "2") (pinfunction "2_2") (pintype "passive"))
      (node (ref "R12") (pin "2") (pinfunction "2_2") (pintype "passive"))
      (node (ref "R13") (pin "1") (pinfunction "1_1") (pintype "passive"))
    )
    (net (code "49") (name "VUSB") (class "Default")
      (node (ref "C26") (pin "2") (pinfunction "2_2") (pintype "passive"))
      (node (ref "J3") (pin "5") (pinfunction "5_5") (pintype "passive"))
      (node (ref "R12") (pin "1") (pinfunction "1_1") (pintype "passive"))
    )
    (net (code "50") (name "unconnected-(J1-Pad1)") (class "Default")
      (node (ref "J1") (pin "1") (pinfunction "1_1") (pintype "passive+no_connect"))
    )
    (net (code "51") (name "unconnected-(J1-Pad2)") (class "Default")
      (node (ref "J1") (pin "2") (pinfunction "2_2") (pintype "passive+no_connect"))
    )
    (net (code "52") (name "unconnected-(J1_DISP-Pad1)") (class "Default")
      (node (ref "J1_DISP") (pin "1") (pinfunction "1_1") (pintype "passive+no_connect"))
    )
    (net (code "53") (name "unconnected-(J1_DISP-Pad2)") (class "Default")
      (node (ref "J1_DISP") (pin "2") (pinfunction "2_2") (pintype "passive+no_connect"))
    )
    (net (code "54") (name "unconnected-(J1_DISP-Pad4)") (class "Default")
      (node (ref "J1_DISP") (pin "4") (pinfunction "4_4") (pintype "passive+no_connect"))
    )
    (net (code "55") (name "unconnected-(J1_DISP-Pad6)") (class "Default")
      (node (ref "J1_DISP") (pin "6") (pinfunction "6_6") (pintype "passive+no_connect"))
    )
    (net (code "56") (name "unconnected-(J1_DISP-Pad8)") (class "Default")
      (node (ref "J1_DISP") (pin "8") (pinfunction "8_8") (pintype "passive+no_connect"))
    )
    (net (code "57") (name "unconnected-(J2-Pad8)") (class "Default")
      (node (ref "J2") (pin "8") (pinfunction "8_8") (pintype "passive+no_connect"))
    )
    (net (code "58") (name "unconnected-(J2-Pad9)") (class "Default")
      (node (ref "J2") (pin "9") (pinfunction "9_9") (pintype "passive+no_connect"))
    )
    (net (code "59") (name "unconnected-(J2-Pad10)") (class "Default")
      (node (ref "J2") (pin "10") (pinfunction "10_10") (pintype "passive+no_connect"))
    )
    (net (code "60") (name "unconnected-(J2_DISP-Pad8)") (class "Default")
      (node (ref "J2_DISP") (pin "8") (pinfunction "8_8") (pintype "passive+no_connect"))
    )
    (net (code "61") (name "unconnected-(J2_DISP-Pad9)") (class "Default")
      (node (ref "J2_DISP") (pin "9") (pinfunction "9_9") (pintype "passive+no_connect"))
    )
    (net (code "62") (name "unconnected-(J2_DISP-Pad10)") (class "Default")
      (node (ref "J2_DISP") (pin "10") (pinfunction "10_10") (pintype "passive+no_connect"))
    )
    (net (code "63") (name "unconnected-(J3-Pad1)") (class "Default")
      (node (ref "J3") (pin "1") (pinfunction "1_1") (pintype "passive+no_connect"))
    )
    (net (code "64") (name "unconnected-(J3-Pad2)") (class "Default")
      (node (ref "J3") (pin "2") (pinfunction "2_2") (pintype "passive+no_connect"))
    )
    (net (code "65") (name "unconnected-(J3-Pad8)") (class "Default")
      (node (ref "J3") (pin "8") (pinfunction "8_8") (pintype "passive+no_connect"))
    )
    (net (code "66") (name "unconnected-(J3_DISP-Pad1)") (class "Default")
      (node (ref "J3_DISP") (pin "1") (pinfunction "1_1") (pintype "passive+no_connect"))
    )
    (net (code "67") (name "unconnected-(J3_DISP-Pad2)") (class "Default")
      (node (ref "J3_DISP") (pin "2") (pinfunction "2_2") (pintype "passive+no_connect"))
    )
    (net (code "68") (name "unconnected-(J3_DISP-Pad4)") (class "Default")
      (node (ref "J3_DISP") (pin "4") (pinfunction "4_4") (pintype "passive+no_connect"))
    )
    (net (code "69") (name "unconnected-(J3_DISP-Pad8)") (class "Default")
      (node (ref "J3_DISP") (pin "8") (pinfunction "8_8") (pintype "passive+no_connect"))
    )
    (net (code "70") (name "unconnected-(J4_DISP-Pad1)") (class "Default")
      (node (ref "J4_DISP") (pin "1") (pinfunction "1_1") (pintype "passive+no_connect"))
    )
    (net (code "71") (name "unconnected-(J4_DISP-Pad2)") (class "Default")
      (node (ref "J4_DISP") (pin "2") (pinfunction "2_2") (pintype "passive+no_connect"))
    )
    (net (code "72") (name "unconnected-(J4_DISP-Pad3)") (class "Default")
      (node (ref "J4_DISP") (pin "3") (pinfunction "3_3") (pintype "passive+no_connect"))
    )
    (net (code "73") (name "unconnected-(J4_DISP-Pad4)") (class "Default")
      (node (ref "J4_DISP") (pin "4") (pinfunction "4_4") (pintype "passive+no_connect"))
    )
    (net (code "74") (name "unconnected-(J4_DISP-Pad5)") (class "Default")
      (node (ref "J4_DISP") (pin "5") (pinfunction "5_5") (pintype "passive+no_connect"))
    )
    (net (code "75") (name "unconnected-(J4_DISP-Pad6)") (class "Default")
      (node (ref "J4_DISP") (pin "6") (pinfunction "6_6") (pintype "passive+no_connect"))
    )
    (net (code "76") (name "unconnected-(Logo Bot-Pad0)") (class "Default")
      (node (ref "Logo Bot") (pin "0") (pinfunction "0_0") (pintype "passive"))
    )
    (net (code "77") (name "unconnected-(Logo ESD-Pad0)") (class "Default")
      (node (ref "Logo ESD") (pin "0") (pinfunction "0_0") (pintype "passive"))
    )
    (net (code "78") (name "unconnected-(Logo Recycling1-Pad0)") (class "Default")
      (node (ref "Logo Recycling1") (pin "0") (pinfunction "0_0") (pintype "passive"))
    )
    (net (code "79") (name "unconnected-(Logo Semtech S-Pad0)") (class "Default")
      (node (ref "Logo Semtech S") (pin "0") (pinfunction "0_0") (pintype "passive"))
    )
    (net (code "80") (name "unconnected-(Logo_LoRA1-Pad0)") (class "Default")
      (node (ref "Logo_LoRA1") (pin "0") (pinfunction "0_0") (pintype "passive"))
    )
    (net (code "81") (name "unconnected-(Logo_LoRA2-Pad0)") (class "Default")
      (node (ref "Logo_LoRA2") (pin "0") (pinfunction "0_0") (pintype "passive"))
    )
  )
)
